# hbridgeB.net
KiCad netlist of a schematic drawn in Altium Designer
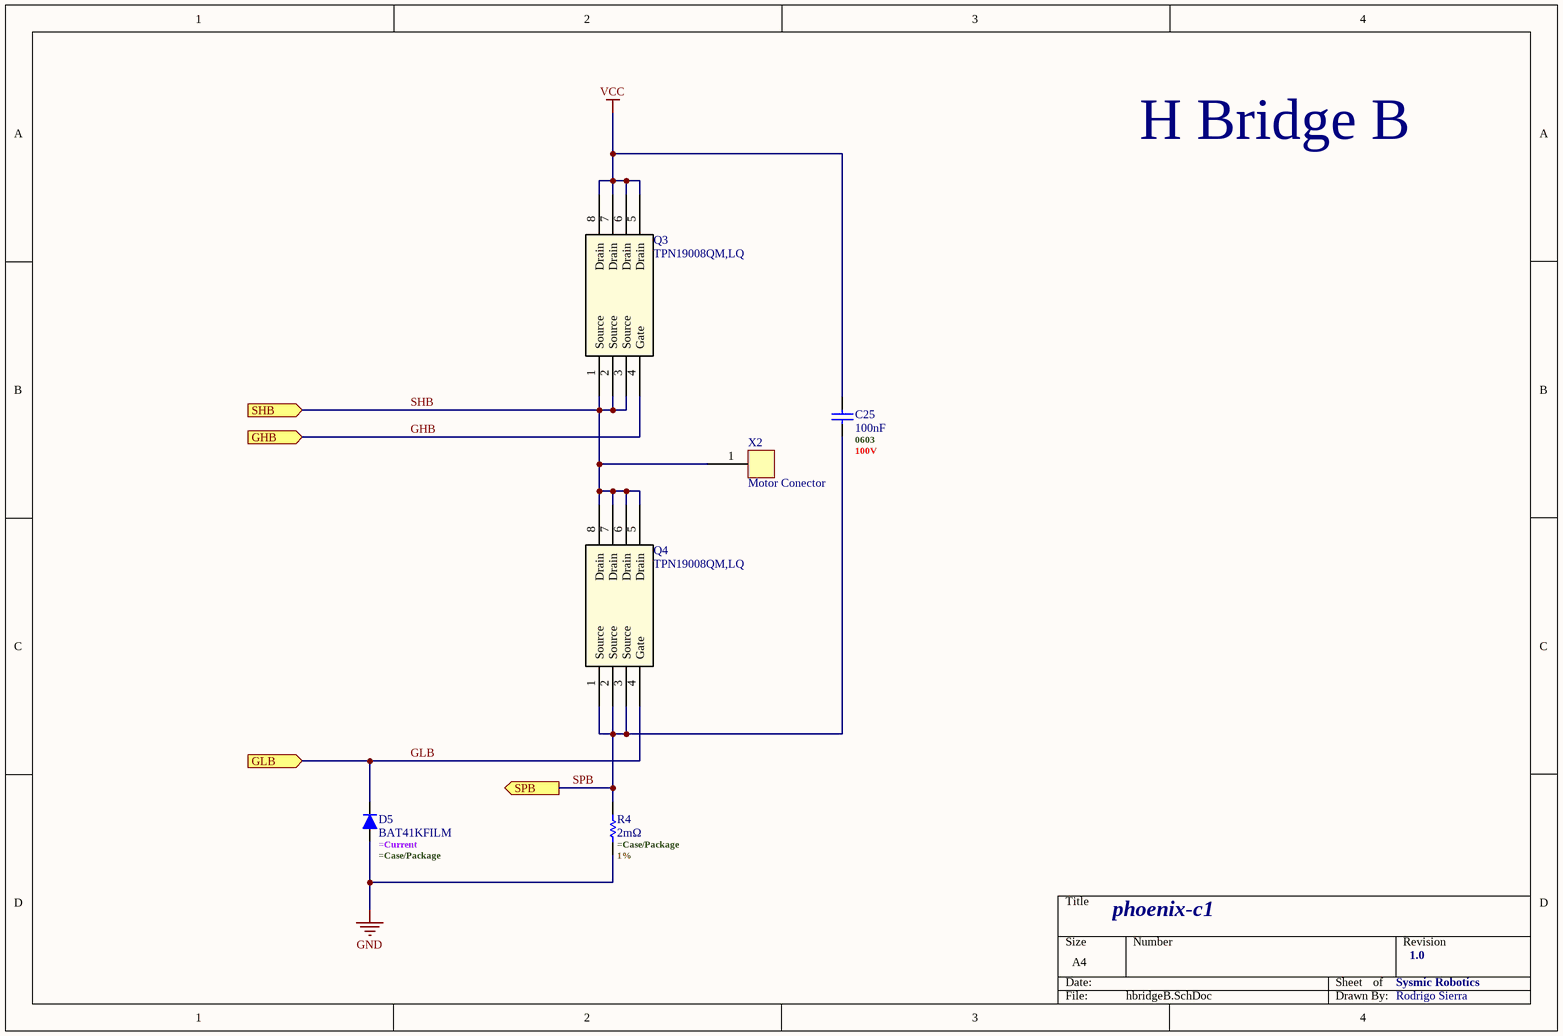
[diagram p0: hbridgeB.SchDoc]

(export (version "E")
  (design (tool "Eeschema 10.0.6"))
  (components
    (comp (ref "C25")
      (value "100nF")
      (footprint "C0603 - MURATA")
      (description "Cap Ceramic 0.1uF 100V X7R 10% Pad SMD 0603 Soft Termination 125C Automotive T/R")
      (fields
        (field (name "MANUFACTURER") "Murata")
        (field (name "MANUFACTURER PART NUMBER") "GCJ188R72A104KA01D")
        (field (name ".CASE/PACKAGE") "0603")
        (field (name ".VOLTAGE RATING (DC)") "100V")
      )
      (libsource (lib "CAP - GCJ188R72A104KA01D") (part "GCJ188R72A104KA01D"))
    )
    (comp (ref "D5")
      (value "BAT41KFILM")
      (footprint "DSOD-523 - STMicroelectronics")
      (description "Low Capacitance Small Signal 200 mA 1 V Schottky Diode Surface Mount - SOD-523")
      (fields (field (name "MANUFACTURER") "STMicroelectronics"))
      (libsource (lib "DIODE - BAT41KFILM") (part "BAT41KFILM"))
    )
    (comp (ref "Q3")
      (value "TPN19008QM,LQ")
      (footprint "8-TSON - TOSHIBA")
      (description "Power MOSFET, N Channel, 80 V, 38 A, 0.0147 ohm, TSON, Surface Mount")
      (fields (field (name "COPYRIGHT") "Copyright (C) 2025 Ultra Librarian. All rights reserved."))
      (libsource (lib "MOSFET - TPN19008QM_LQ") (part "TPN19008QM,LQ"))
    )
    (comp (ref "Q4")
      (value "TPN19008QM,LQ")
      (footprint "8-TSON - TOSHIBA")
      (description "Power MOSFET, N Channel, 80 V, 38 A, 0.0147 ohm, TSON, Surface Mount")
      (fields (field (name "COPYRIGHT") "Copyright (C) 2025 Ultra Librarian. All rights reserved."))
      (libsource (lib "MOSFET - TPN19008QM_LQ") (part "TPN19008QM,LQ"))
    )
    (comp (ref "R4")
      (value "2mΩ")
      (footprint "R0805 - SEI")
      (description "Res Metal Alloy 0805 0.002 Ohm 1% 1W ±75ppm/C Pad SMD T/R Automotive AEC-Q200")
      (fields
        (field (name "MANUFACTURER") "Stackpole Electronics")
        (field (name "MANUFACTURER PART NUMBER") "CSSH0805FT2L00")
        (field (name ".TOLERANCE") "1%")
      )
      (libsource (lib "RES - CSSH0805FT2L00") (part "CSSH0805FT2L00"))
    )
    (comp (ref "X2")
      (value "Motor Conector")
      (footprint "CONN_PHASE01x01")
      (description "Generic connector, single row")
      (libsource (lib "CONN - MOTOR PHASE") (part "Conn_01x01"))
    )
  )
  (nets
    (net (code "1") (name "/GHB") (class "Default")
      (node (ref "Q3") (pin "4") (pinfunction "Gate_4") (pintype "passive"))
    )
    (net (code "2") (name "/GLB") (class "Default")
      (node (ref "D5") (pin "1") (pinfunction "1_1") (pintype "passive"))
      (node (ref "Q4") (pin "4") (pinfunction "Gate_4") (pintype "passive"))
    )
    (net (code "3") (name "/SHB") (class "Default")
      (node (ref "Q3") (pin "1") (pinfunction "Source_1") (pintype "passive"))
      (node (ref "Q3") (pin "2") (pinfunction "Source_2") (pintype "passive"))
      (node (ref "Q3") (pin "3") (pinfunction "Source_3") (pintype "passive"))
      (node (ref "Q4") (pin "5") (pinfunction "Drain_5") (pintype "passive"))
      (node (ref "Q4") (pin "6") (pinfunction "Drain_6") (pintype "passive"))
      (node (ref "Q4") (pin "7") (pinfunction "Drain_7") (pintype "passive"))
      (node (ref "Q4") (pin "8") (pinfunction "Drain_8") (pintype "passive"))
      (node (ref "X2") (pin "1") (pinfunction "Conn_1") (pintype "passive"))
    )
    (net (code "4") (name "/SPB") (class "Default")
      (node (ref "C25") (pin "1") (pinfunction "1_1") (pintype "passive"))
      (node (ref "Q4") (pin "1") (pinfunction "Source_1") (pintype "passive"))
      (node (ref "Q4") (pin "2") (pinfunction "Source_2") (pintype "passive"))
      (node (ref "Q4") (pin "3") (pinfunction "Source_3") (pintype "passive"))
      (node (ref "R4") (pin "2") (pinfunction "2_2") (pintype "passive"))
    )
    (net (code "5") (name "GND") (class "Default")
      (node (ref "D5") (pin "2") (pinfunction "2_2") (pintype "passive"))
      (node (ref "R4") (pin "1") (pinfunction "1_1") (pintype "passive"))
    )
    (net (code "6") (name "VCC") (class "Default")
      (node (ref "C25") (pin "2") (pinfunction "2_2") (pintype "passive"))
      (node (ref "Q3") (pin "5") (pinfunction "Drain_5") (pintype "passive"))
      (node (ref "Q3") (pin "6") (pinfunction "Drain_6") (pintype "passive"))
      (node (ref "Q3") (pin "7") (pinfunction "Drain_7") (pintype "passive"))
      (node (ref "Q3") (pin "8") (pinfunction "Drain_8") (pintype "passive"))
    )
  )
)
